# 4_inputs.net
KiCad netlist of a schematic drawn in EAGLE
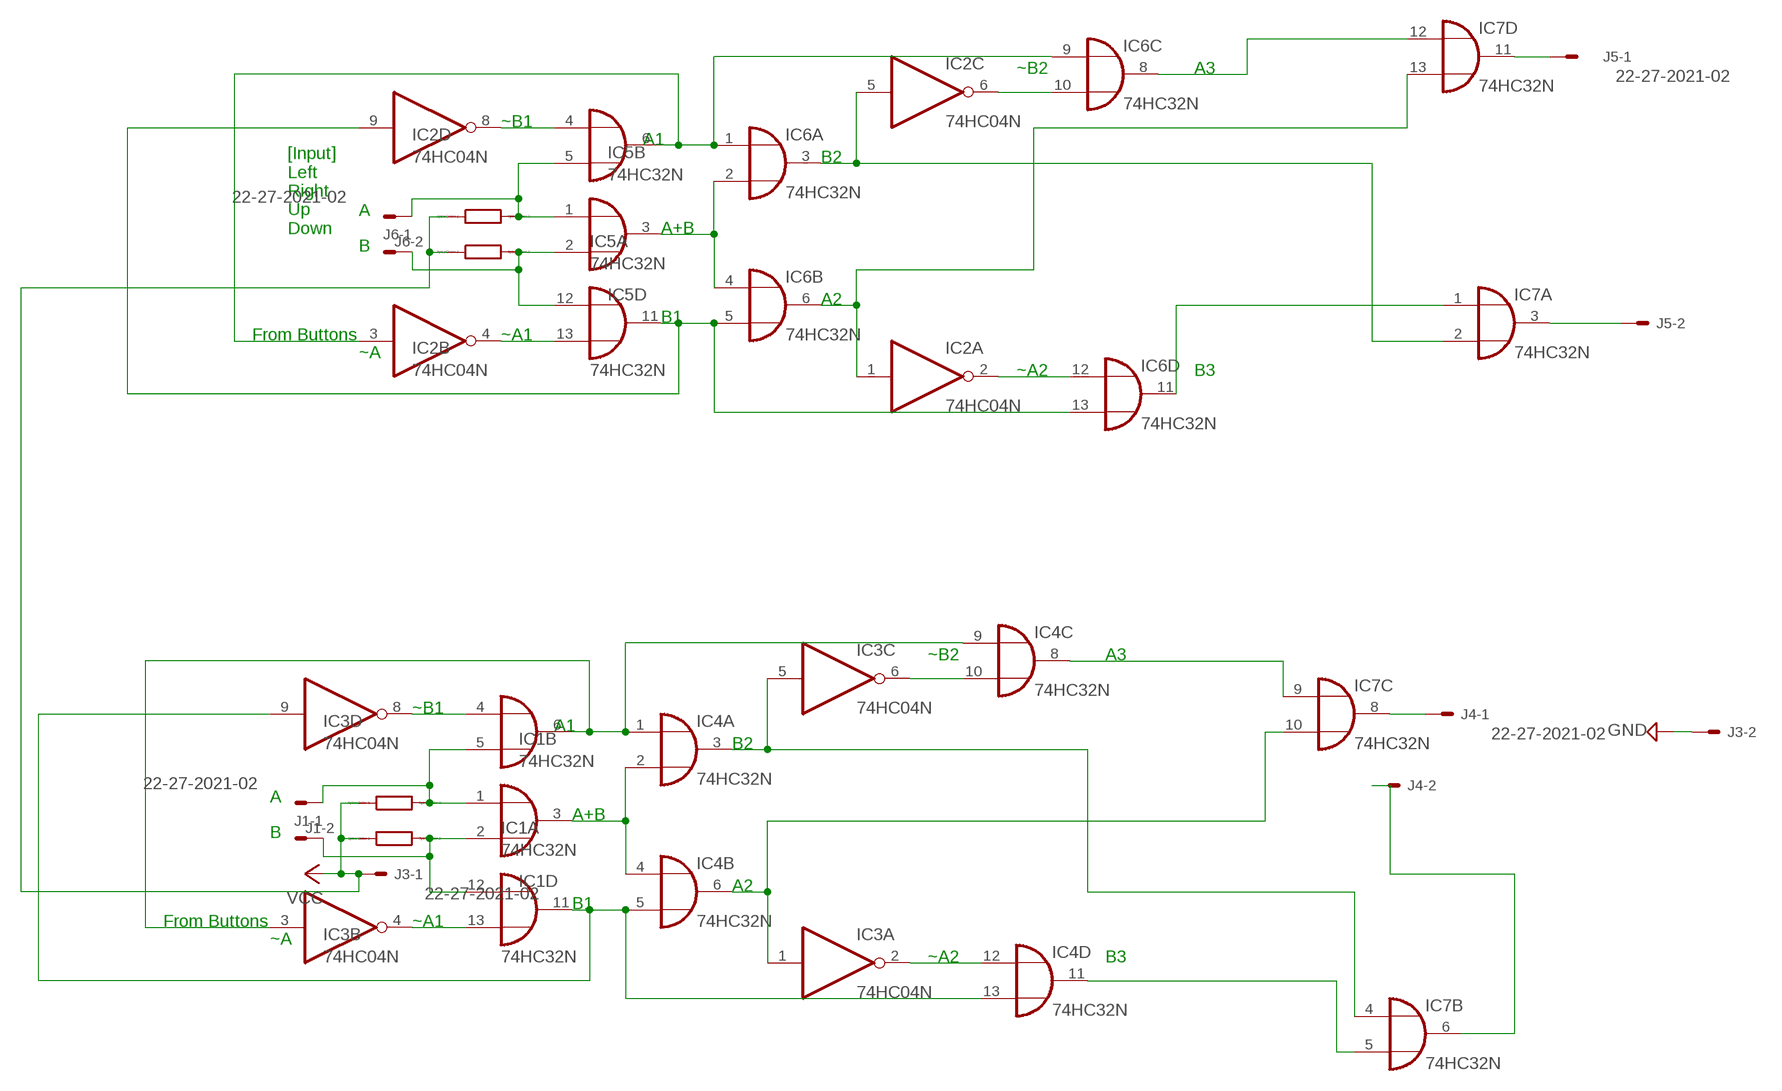
[diagram p0: schematic, sheet 1]

(export (version "E")
  (design (tool "Eeschema 10.0.6"))
  (components
    (comp (ref "IC1")
      (value "74HC32N")
      (footprint "eagle-import:DIL14")
      (libsource (lib "eagle-import") (part "7432NHC"))
    )
    (comp (ref "IC2")
      (value "74HC04N")
      (footprint "eagle-import:DIL14")
      (libsource (lib "eagle-import") (part "7404NHC"))
    )
    (comp (ref "IC3")
      (value "74HC04N")
      (footprint "eagle-import:DIL14")
      (libsource (lib "eagle-import") (part "7404NHC"))
    )
    (comp (ref "IC4")
      (value "74HC32N")
      (footprint "eagle-import:DIL14")
      (libsource (lib "eagle-import") (part "7432NHC"))
    )
    (comp (ref "IC5")
      (value "74HC32N")
      (footprint "eagle-import:DIL14")
      (libsource (lib "eagle-import") (part "7432NHC"))
    )
    (comp (ref "IC6")
      (value "74HC32N")
      (footprint "eagle-import:DIL14")
      (libsource (lib "eagle-import") (part "7432NHC"))
    )
    (comp (ref "IC7")
      (value "74HC32N")
      (footprint "eagle-import:DIL14")
      (libsource (lib "eagle-import") (part "7432NHC"))
    )
    (comp (ref "J1")
      (value "22-27-2021-02")
      (footprint "eagle-import:6410-02")
      (fields (field (name "MF") "MOLEX"))
      (libsource (lib "eagle-import") (part "22-?-0227-2021"))
    )
    (comp (ref "J3")
      (value "22-27-2021-02")
      (footprint "eagle-import:6410-02")
      (fields (field (name "MF") "MOLEX"))
      (libsource (lib "eagle-import") (part "22-?-0227-2021"))
    )
    (comp (ref "J4")
      (value "22-27-2021-02")
      (footprint "eagle-import:6410-02")
      (fields (field (name "MF") "MOLEX"))
      (libsource (lib "eagle-import") (part "22-?-0227-2021"))
    )
    (comp (ref "J5")
      (value "22-27-2021-02")
      (footprint "eagle-import:6410-02")
      (fields (field (name "MF") "MOLEX"))
      (libsource (lib "eagle-import") (part "22-?-0227-2021"))
    )
    (comp (ref "J6")
      (value "22-27-2021-02")
      (footprint "eagle-import:6410-02")
      (fields (field (name "MF") "MOLEX"))
      (libsource (lib "eagle-import") (part "22-?-0227-2021"))
    )
    (comp (ref "R1")
      (value "R0204/7")
      (footprint "eagle-import:0204_7")
      (libsource (lib "eagle-import") (part "R0204/7"))
    )
    (comp (ref "R2")
      (value "R0204/7")
      (footprint "eagle-import:0204_7")
      (libsource (lib "eagle-import") (part "R0204/7"))
    )
    (comp (ref "R3")
      (value "R0204/7")
      (footprint "eagle-import:0204_7")
      (libsource (lib "eagle-import") (part "R0204/7"))
    )
    (comp (ref "R4")
      (value "R0204/7")
      (footprint "eagle-import:0204_7")
      (libsource (lib "eagle-import") (part "R0204/7"))
    )
  )
  (nets
    (net (code "1") (name "GND") (class "Default")
      (node (ref "J3") (pin "2") (pinfunction "S_2") (pintype "passive"))
    )
    (net (code "2") (name "Net-(IC1A-I0)") (class "Default")
      (node (ref "IC1") (pin "1") (pinfunction "I0_1") (pintype "input"))
      (node (ref "IC1") (pin "5") (pinfunction "I1_5") (pintype "input"))
      (node (ref "J1") (pin "1") (pinfunction "S_1") (pintype "passive"))
      (node (ref "R3") (pin "2") (pinfunction "2_2") (pintype "passive"))
    )
    (net (code "3") (name "Net-(IC1A-I1)") (class "Default")
      (node (ref "IC1") (pin "12") (pinfunction "I0_12") (pintype "input"))
      (node (ref "IC1") (pin "2") (pinfunction "I1_2") (pintype "input"))
      (node (ref "J1") (pin "2") (pinfunction "S_2") (pintype "passive"))
      (node (ref "R4") (pin "2") (pinfunction "2_2") (pintype "passive"))
    )
    (net (code "4") (name "Net-(IC1A-O)") (class "Default")
      (node (ref "IC1") (pin "3") (pinfunction "O_3") (pintype "output"))
      (node (ref "IC4") (pin "2") (pinfunction "I1_2") (pintype "input"))
      (node (ref "IC4") (pin "4") (pinfunction "I0_4") (pintype "input"))
    )
    (net (code "5") (name "Net-(IC1B-I0)") (class "Default")
      (node (ref "IC1") (pin "4") (pinfunction "I0_4") (pintype "input"))
      (node (ref "IC3") (pin "8") (pinfunction "O_8") (pintype "output"))
    )
    (net (code "6") (name "Net-(IC1B-O)") (class "Default")
      (node (ref "IC1") (pin "6") (pinfunction "O_6") (pintype "output"))
      (node (ref "IC3") (pin "3") (pinfunction "I_3") (pintype "input"))
      (node (ref "IC4") (pin "1") (pinfunction "I0_1") (pintype "input"))
      (node (ref "IC4") (pin "9") (pinfunction "I0_9") (pintype "input"))
    )
    (net (code "7") (name "Net-(IC1D-I1)") (class "Default")
      (node (ref "IC1") (pin "13") (pinfunction "I1_13") (pintype "input"))
      (node (ref "IC3") (pin "4") (pinfunction "O_4") (pintype "output"))
    )
    (net (code "8") (name "Net-(IC1D-O)") (class "Default")
      (node (ref "IC1") (pin "11") (pinfunction "O_11") (pintype "output"))
      (node (ref "IC3") (pin "9") (pinfunction "I_9") (pintype "input"))
      (node (ref "IC4") (pin "13") (pinfunction "I1_13") (pintype "input"))
      (node (ref "IC4") (pin "5") (pinfunction "I1_5") (pintype "input"))
    )
    (net (code "9") (name "Net-(IC2A-I)") (class "Default")
      (node (ref "IC2") (pin "1") (pinfunction "I_1") (pintype "input"))
      (node (ref "IC6") (pin "6") (pinfunction "O_6") (pintype "output"))
      (node (ref "IC7") (pin "13") (pinfunction "I1_13") (pintype "input"))
    )
    (net (code "10") (name "Net-(IC2A-O)") (class "Default")
      (node (ref "IC2") (pin "2") (pinfunction "O_2") (pintype "output"))
      (node (ref "IC6") (pin "12") (pinfunction "I0_12") (pintype "input"))
    )
    (net (code "11") (name "Net-(IC2B-I)") (class "Default")
      (node (ref "IC2") (pin "3") (pinfunction "I_3") (pintype "input"))
      (node (ref "IC5") (pin "6") (pinfunction "O_6") (pintype "output"))
      (node (ref "IC6") (pin "1") (pinfunction "I0_1") (pintype "input"))
      (node (ref "IC6") (pin "9") (pinfunction "I0_9") (pintype "input"))
    )
    (net (code "12") (name "Net-(IC2B-O)") (class "Default")
      (node (ref "IC2") (pin "4") (pinfunction "O_4") (pintype "output"))
      (node (ref "IC5") (pin "13") (pinfunction "I1_13") (pintype "input"))
    )
    (net (code "13") (name "Net-(IC2C-I)") (class "Default")
      (node (ref "IC2") (pin "5") (pinfunction "I_5") (pintype "input"))
      (node (ref "IC6") (pin "3") (pinfunction "O_3") (pintype "output"))
      (node (ref "IC7") (pin "2") (pinfunction "I1_2") (pintype "input"))
    )
    (net (code "14") (name "Net-(IC2C-O)") (class "Default")
      (node (ref "IC2") (pin "6") (pinfunction "O_6") (pintype "output"))
      (node (ref "IC6") (pin "10") (pinfunction "I1_10") (pintype "input"))
    )
    (net (code "15") (name "Net-(IC2D-I)") (class "Default")
      (node (ref "IC2") (pin "9") (pinfunction "I_9") (pintype "input"))
      (node (ref "IC5") (pin "11") (pinfunction "O_11") (pintype "output"))
      (node (ref "IC6") (pin "13") (pinfunction "I1_13") (pintype "input"))
      (node (ref "IC6") (pin "5") (pinfunction "I1_5") (pintype "input"))
    )
    (net (code "16") (name "Net-(IC2D-O)") (class "Default")
      (node (ref "IC2") (pin "8") (pinfunction "O_8") (pintype "output"))
      (node (ref "IC5") (pin "4") (pinfunction "I0_4") (pintype "input"))
    )
    (net (code "17") (name "Net-(IC3A-I)") (class "Default")
      (node (ref "IC3") (pin "1") (pinfunction "I_1") (pintype "input"))
      (node (ref "IC4") (pin "6") (pinfunction "O_6") (pintype "output"))
      (node (ref "IC7") (pin "10") (pinfunction "I1_10") (pintype "input"))
    )
    (net (code "18") (name "Net-(IC3A-O)") (class "Default")
      (node (ref "IC3") (pin "2") (pinfunction "O_2") (pintype "output"))
      (node (ref "IC4") (pin "12") (pinfunction "I0_12") (pintype "input"))
    )
    (net (code "19") (name "Net-(IC3C-I)") (class "Default")
      (node (ref "IC3") (pin "5") (pinfunction "I_5") (pintype "input"))
      (node (ref "IC4") (pin "3") (pinfunction "O_3") (pintype "output"))
      (node (ref "IC7") (pin "4") (pinfunction "I0_4") (pintype "input"))
    )
    (net (code "20") (name "Net-(IC3C-O)") (class "Default")
      (node (ref "IC3") (pin "6") (pinfunction "O_6") (pintype "output"))
      (node (ref "IC4") (pin "10") (pinfunction "I1_10") (pintype "input"))
    )
    (net (code "21") (name "Net-(IC4C-O)") (class "Default")
      (node (ref "IC4") (pin "8") (pinfunction "O_8") (pintype "output"))
      (node (ref "IC7") (pin "9") (pinfunction "I0_9") (pintype "input"))
    )
    (net (code "22") (name "Net-(IC4D-O)") (class "Default")
      (node (ref "IC4") (pin "11") (pinfunction "O_11") (pintype "output"))
      (node (ref "IC7") (pin "5") (pinfunction "I1_5") (pintype "input"))
    )
    (net (code "23") (name "Net-(IC5A-I0)") (class "Default")
      (node (ref "IC5") (pin "1") (pinfunction "I0_1") (pintype "input"))
      (node (ref "IC5") (pin "5") (pinfunction "I1_5") (pintype "input"))
      (node (ref "J6") (pin "1") (pinfunction "S_1") (pintype "passive"))
      (node (ref "R1") (pin "2") (pinfunction "2_2") (pintype "passive"))
    )
    (net (code "24") (name "Net-(IC5A-I1)") (class "Default")
      (node (ref "IC5") (pin "12") (pinfunction "I0_12") (pintype "input"))
      (node (ref "IC5") (pin "2") (pinfunction "I1_2") (pintype "input"))
      (node (ref "J6") (pin "2") (pinfunction "S_2") (pintype "passive"))
      (node (ref "R2") (pin "2") (pinfunction "2_2") (pintype "passive"))
    )
    (net (code "25") (name "Net-(IC5A-O)") (class "Default")
      (node (ref "IC5") (pin "3") (pinfunction "O_3") (pintype "output"))
      (node (ref "IC6") (pin "2") (pinfunction "I1_2") (pintype "input"))
      (node (ref "IC6") (pin "4") (pinfunction "I0_4") (pintype "input"))
    )
    (net (code "26") (name "Net-(IC6C-O)") (class "Default")
      (node (ref "IC6") (pin "8") (pinfunction "O_8") (pintype "output"))
      (node (ref "IC7") (pin "12") (pinfunction "I0_12") (pintype "input"))
    )
    (net (code "27") (name "Net-(IC6D-O)") (class "Default")
      (node (ref "IC6") (pin "11") (pinfunction "O_11") (pintype "output"))
      (node (ref "IC7") (pin "1") (pinfunction "I0_1") (pintype "input"))
    )
    (net (code "28") (name "Net-(IC7A-O)") (class "Default")
      (node (ref "IC7") (pin "3") (pinfunction "O_3") (pintype "output"))
      (node (ref "J5") (pin "2") (pinfunction "S_2") (pintype "passive"))
    )
    (net (code "29") (name "Net-(IC7B-O)") (class "Default")
      (node (ref "IC7") (pin "6") (pinfunction "O_6") (pintype "output"))
      (node (ref "J4") (pin "2") (pinfunction "S_2") (pintype "passive"))
    )
    (net (code "30") (name "Net-(IC7C-O)") (class "Default")
      (node (ref "IC7") (pin "8") (pinfunction "O_8") (pintype "output"))
      (node (ref "J4") (pin "1") (pinfunction "S_1") (pintype "passive"))
    )
    (net (code "31") (name "Net-(IC7D-O)") (class "Default")
      (node (ref "IC7") (pin "11") (pinfunction "O_11") (pintype "output"))
      (node (ref "J5") (pin "1") (pinfunction "S_1") (pintype "passive"))
    )
    (net (code "32") (name "VCC") (class "Default")
      (node (ref "J3") (pin "1") (pinfunction "S_1") (pintype "passive"))
      (node (ref "R1") (pin "1") (pinfunction "1_1") (pintype "passive"))
      (node (ref "R2") (pin "1") (pinfunction "1_1") (pintype "passive"))
      (node (ref "R3") (pin "1") (pinfunction "1_1") (pintype "passive"))
      (node (ref "R4") (pin "1") (pinfunction "1_1") (pintype "passive"))
    )
  )
)
